# Schematic_EasyEDA.net
KiCad netlist of a schematic drawn in EasyEDA
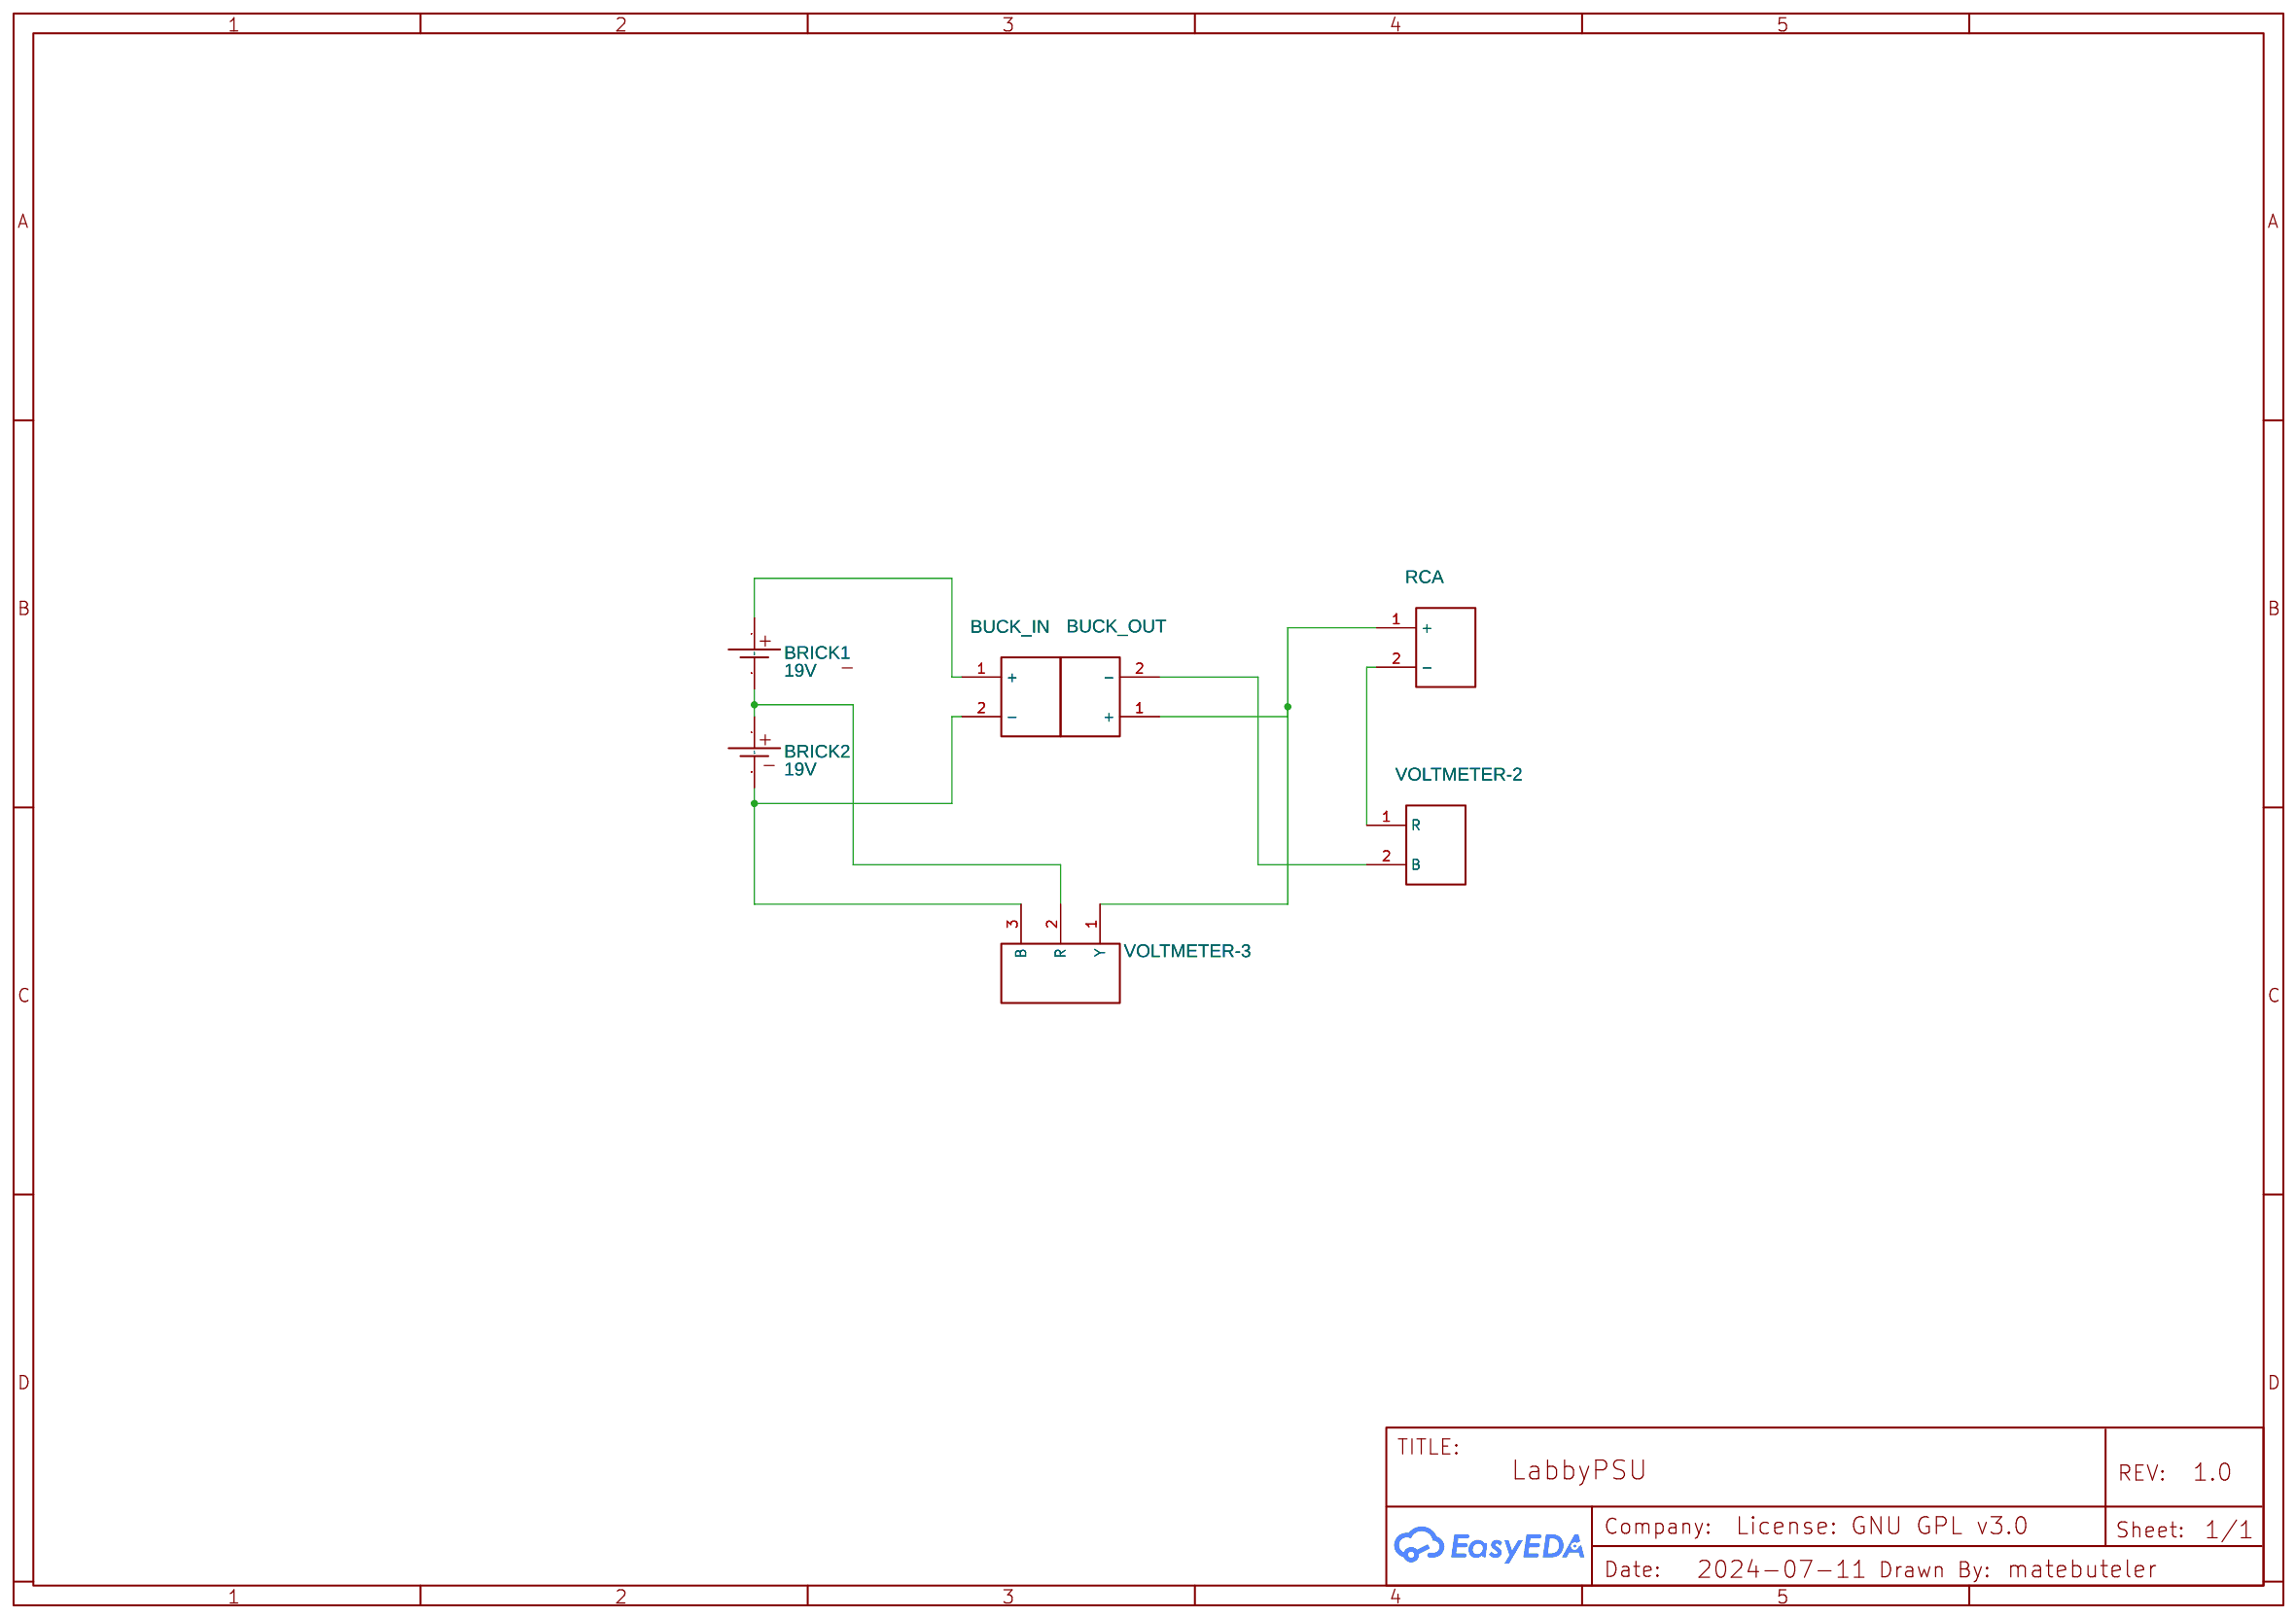
[diagram p0: schematic sheet]

(export (version "E")
  (design (tool "Eeschema 10.0.6"))
  (components
    (comp (ref "BRICK1") (value "19V") (libsource (lib "") (part "SOURCE DC")))
    (comp (ref "BRICK2") (value "19V") (libsource (lib "") (part "SOURCE DC_1")))
    (comp (ref "BUCK_IN")
      (value "MKDSN1.5/2-5.08")
      (fields
        (field (name "Manufacturer Part") "1729128")
        (field (name "Manufacturer") "Phoenix Contact(菲尼克斯)")
      )
      (libsource (lib "") (part "MKDSN1.5/2-5.08_1"))
    )
    (comp (ref "BUCK_OUT")
      (value "MKDSN1.5/2-5.08")
      (fields
        (field (name "Manufacturer Part") "1729128")
        (field (name "Manufacturer") "Phoenix Contact(菲尼克斯)")
      )
      (libsource (lib "") (part "MKDSN1.5/2-5.08"))
    )
    (comp (ref "RCA")
      (value "MKDSN1.5/2-5.08")
      (fields
        (field (name "Manufacturer Part") "1729128")
        (field (name "Manufacturer") "Phoenix Contact(菲尼克斯)")
      )
      (libsource (lib "") (part "MKDSN1.5/2-5.08_2"))
    )
    (comp (ref "VOLTMETER-2")
      (value "MKDSN1.5/2-5.08")
      (fields
        (field (name "Manufacturer Part") "1729128")
        (field (name "Manufacturer") "Phoenix Contact(菲尼克斯)")
      )
      (libsource (lib "") (part "MKDSN1.5/2-5.08_3"))
    )
    (comp (ref "VOLTMETER-3")
      (value "MKDSN1.5/3-5.08")
      (fields
        (field (name "Manufacturer Part") "1729131")
        (field (name "Manufacturer") "Phoenix Contact(菲尼克斯)")
      )
      (libsource (lib "") (part "MKDSN1.5/3-5.08"))
    )
  )
  (nets
    (net (code "1") (name "Net-(BRICK1-+)") (class "Default")
      (node (ref "BRICK1") (pin "1") (pinfunction "+_1") (pintype "unspecified"))
      (node (ref "BUCK_IN") (pin "1") (pinfunction "+_1") (pintype "unspecified"))
    )
    (net (code "2") (name "Net-(BRICK1--)") (class "Default")
      (node (ref "BRICK1") (pin "2") (pinfunction "-_2") (pintype "unspecified"))
      (node (ref "BRICK2") (pin "1") (pinfunction "+_1") (pintype "unspecified"))
      (node (ref "VOLTMETER-3") (pin "2") (pinfunction "R_2") (pintype "unspecified"))
    )
    (net (code "3") (name "Net-(BRICK2--)") (class "Default")
      (node (ref "BRICK2") (pin "2") (pinfunction "-_2") (pintype "unspecified"))
      (node (ref "BUCK_IN") (pin "2") (pinfunction "-_2") (pintype "unspecified"))
      (node (ref "VOLTMETER-3") (pin "3") (pinfunction "B_3") (pintype "unspecified"))
    )
    (net (code "4") (name "Net-(BUCK_OUT-+)") (class "Default")
      (node (ref "BUCK_OUT") (pin "1") (pinfunction "+_1") (pintype "unspecified"))
      (node (ref "RCA") (pin "1") (pinfunction "+_1") (pintype "unspecified"))
      (node (ref "VOLTMETER-3") (pin "1") (pinfunction "Y_1") (pintype "unspecified"))
    )
    (net (code "5") (name "Net-(BUCK_OUT--)") (class "Default")
      (node (ref "BUCK_OUT") (pin "2") (pinfunction "-_2") (pintype "unspecified"))
      (node (ref "VOLTMETER-2") (pin "2") (pinfunction "B_2") (pintype "unspecified"))
    )
    (net (code "6") (name "Net-(RCA--)") (class "Default")
      (node (ref "RCA") (pin "2") (pinfunction "-_2") (pintype "unspecified"))
      (node (ref "VOLTMETER-2") (pin "1") (pinfunction "R_1") (pintype "unspecified"))
    )
  )
)
